# Embedded_II_MAIN_BOARD.net
KiCad netlist of a schematic drawn in EAGLE
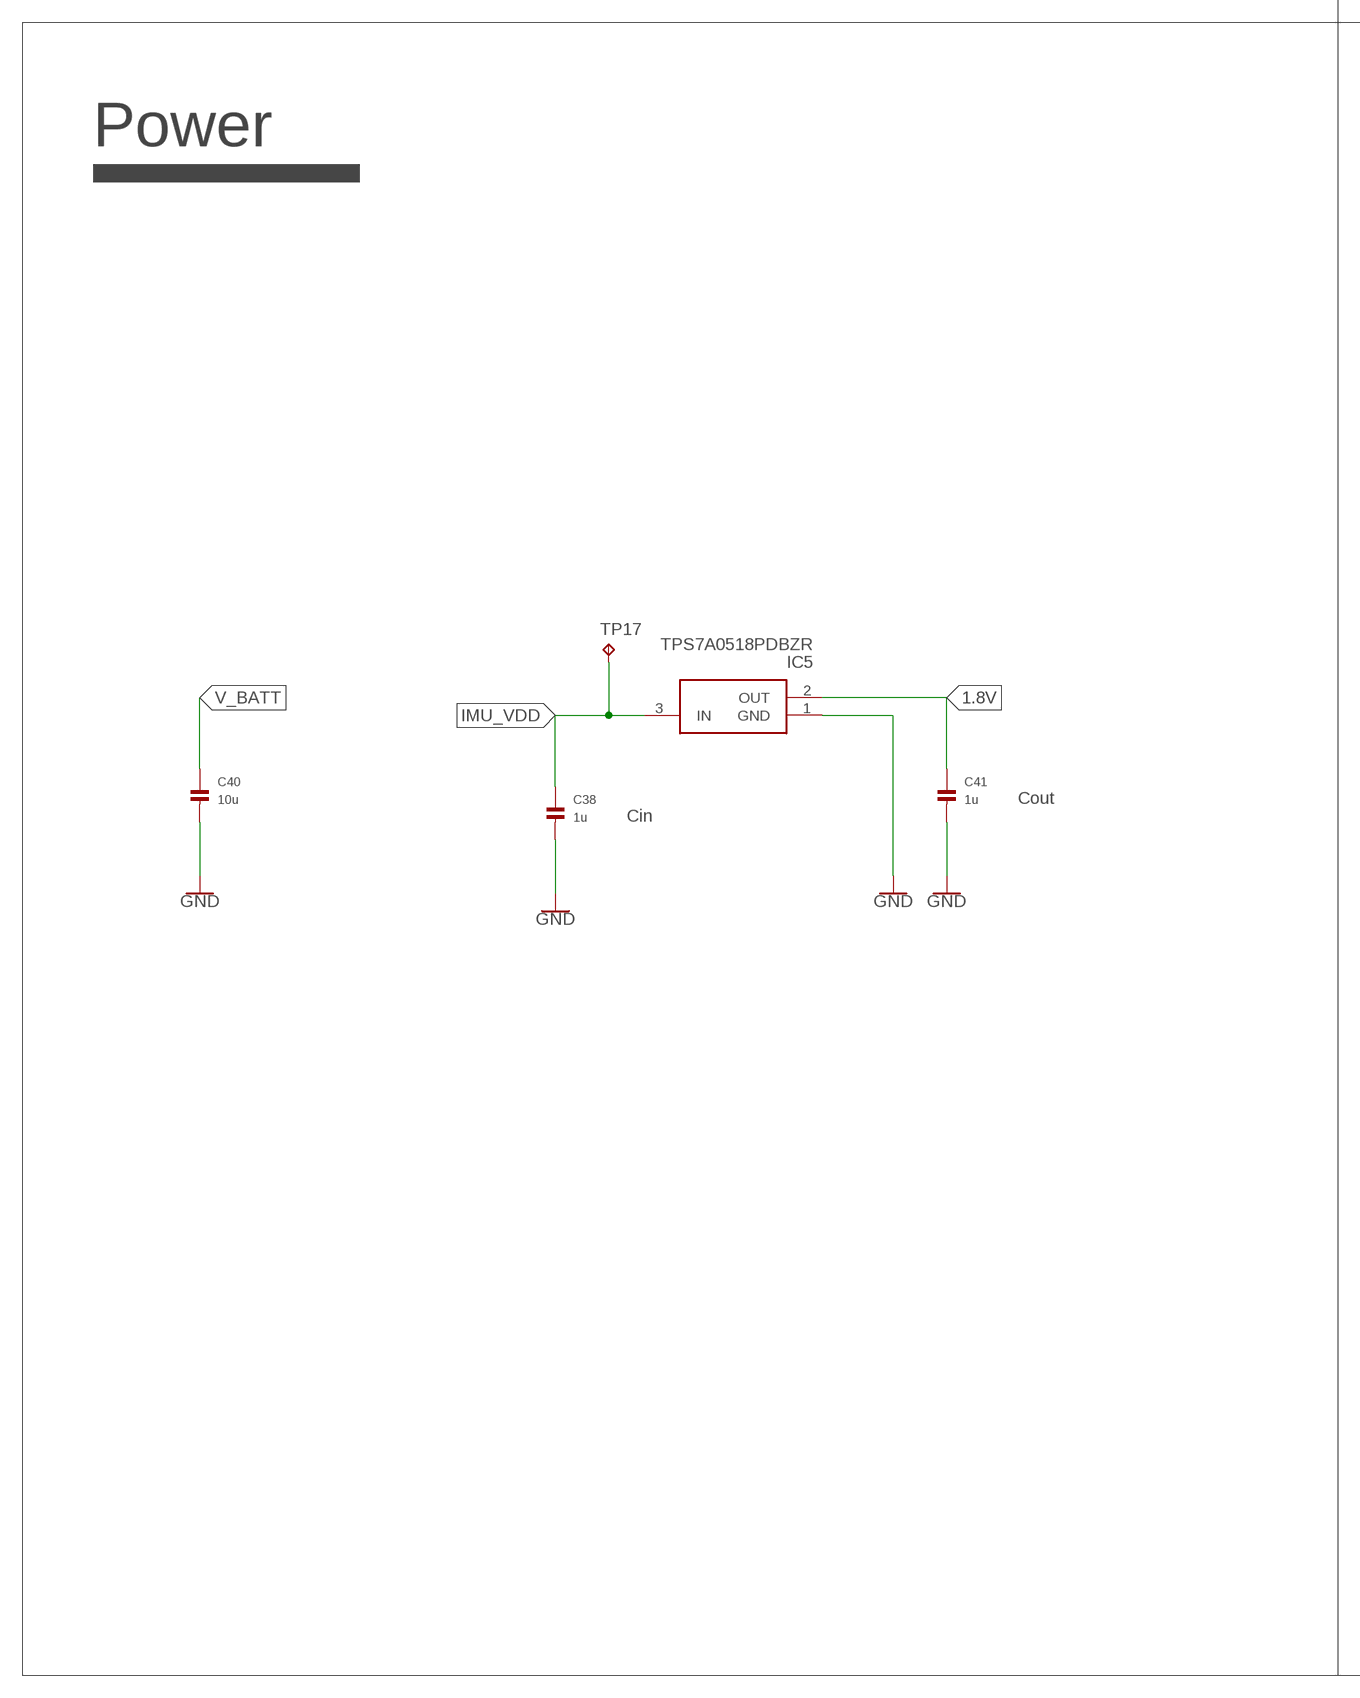
[diagram p0: schematic, sheet 1, part 1 of 2]
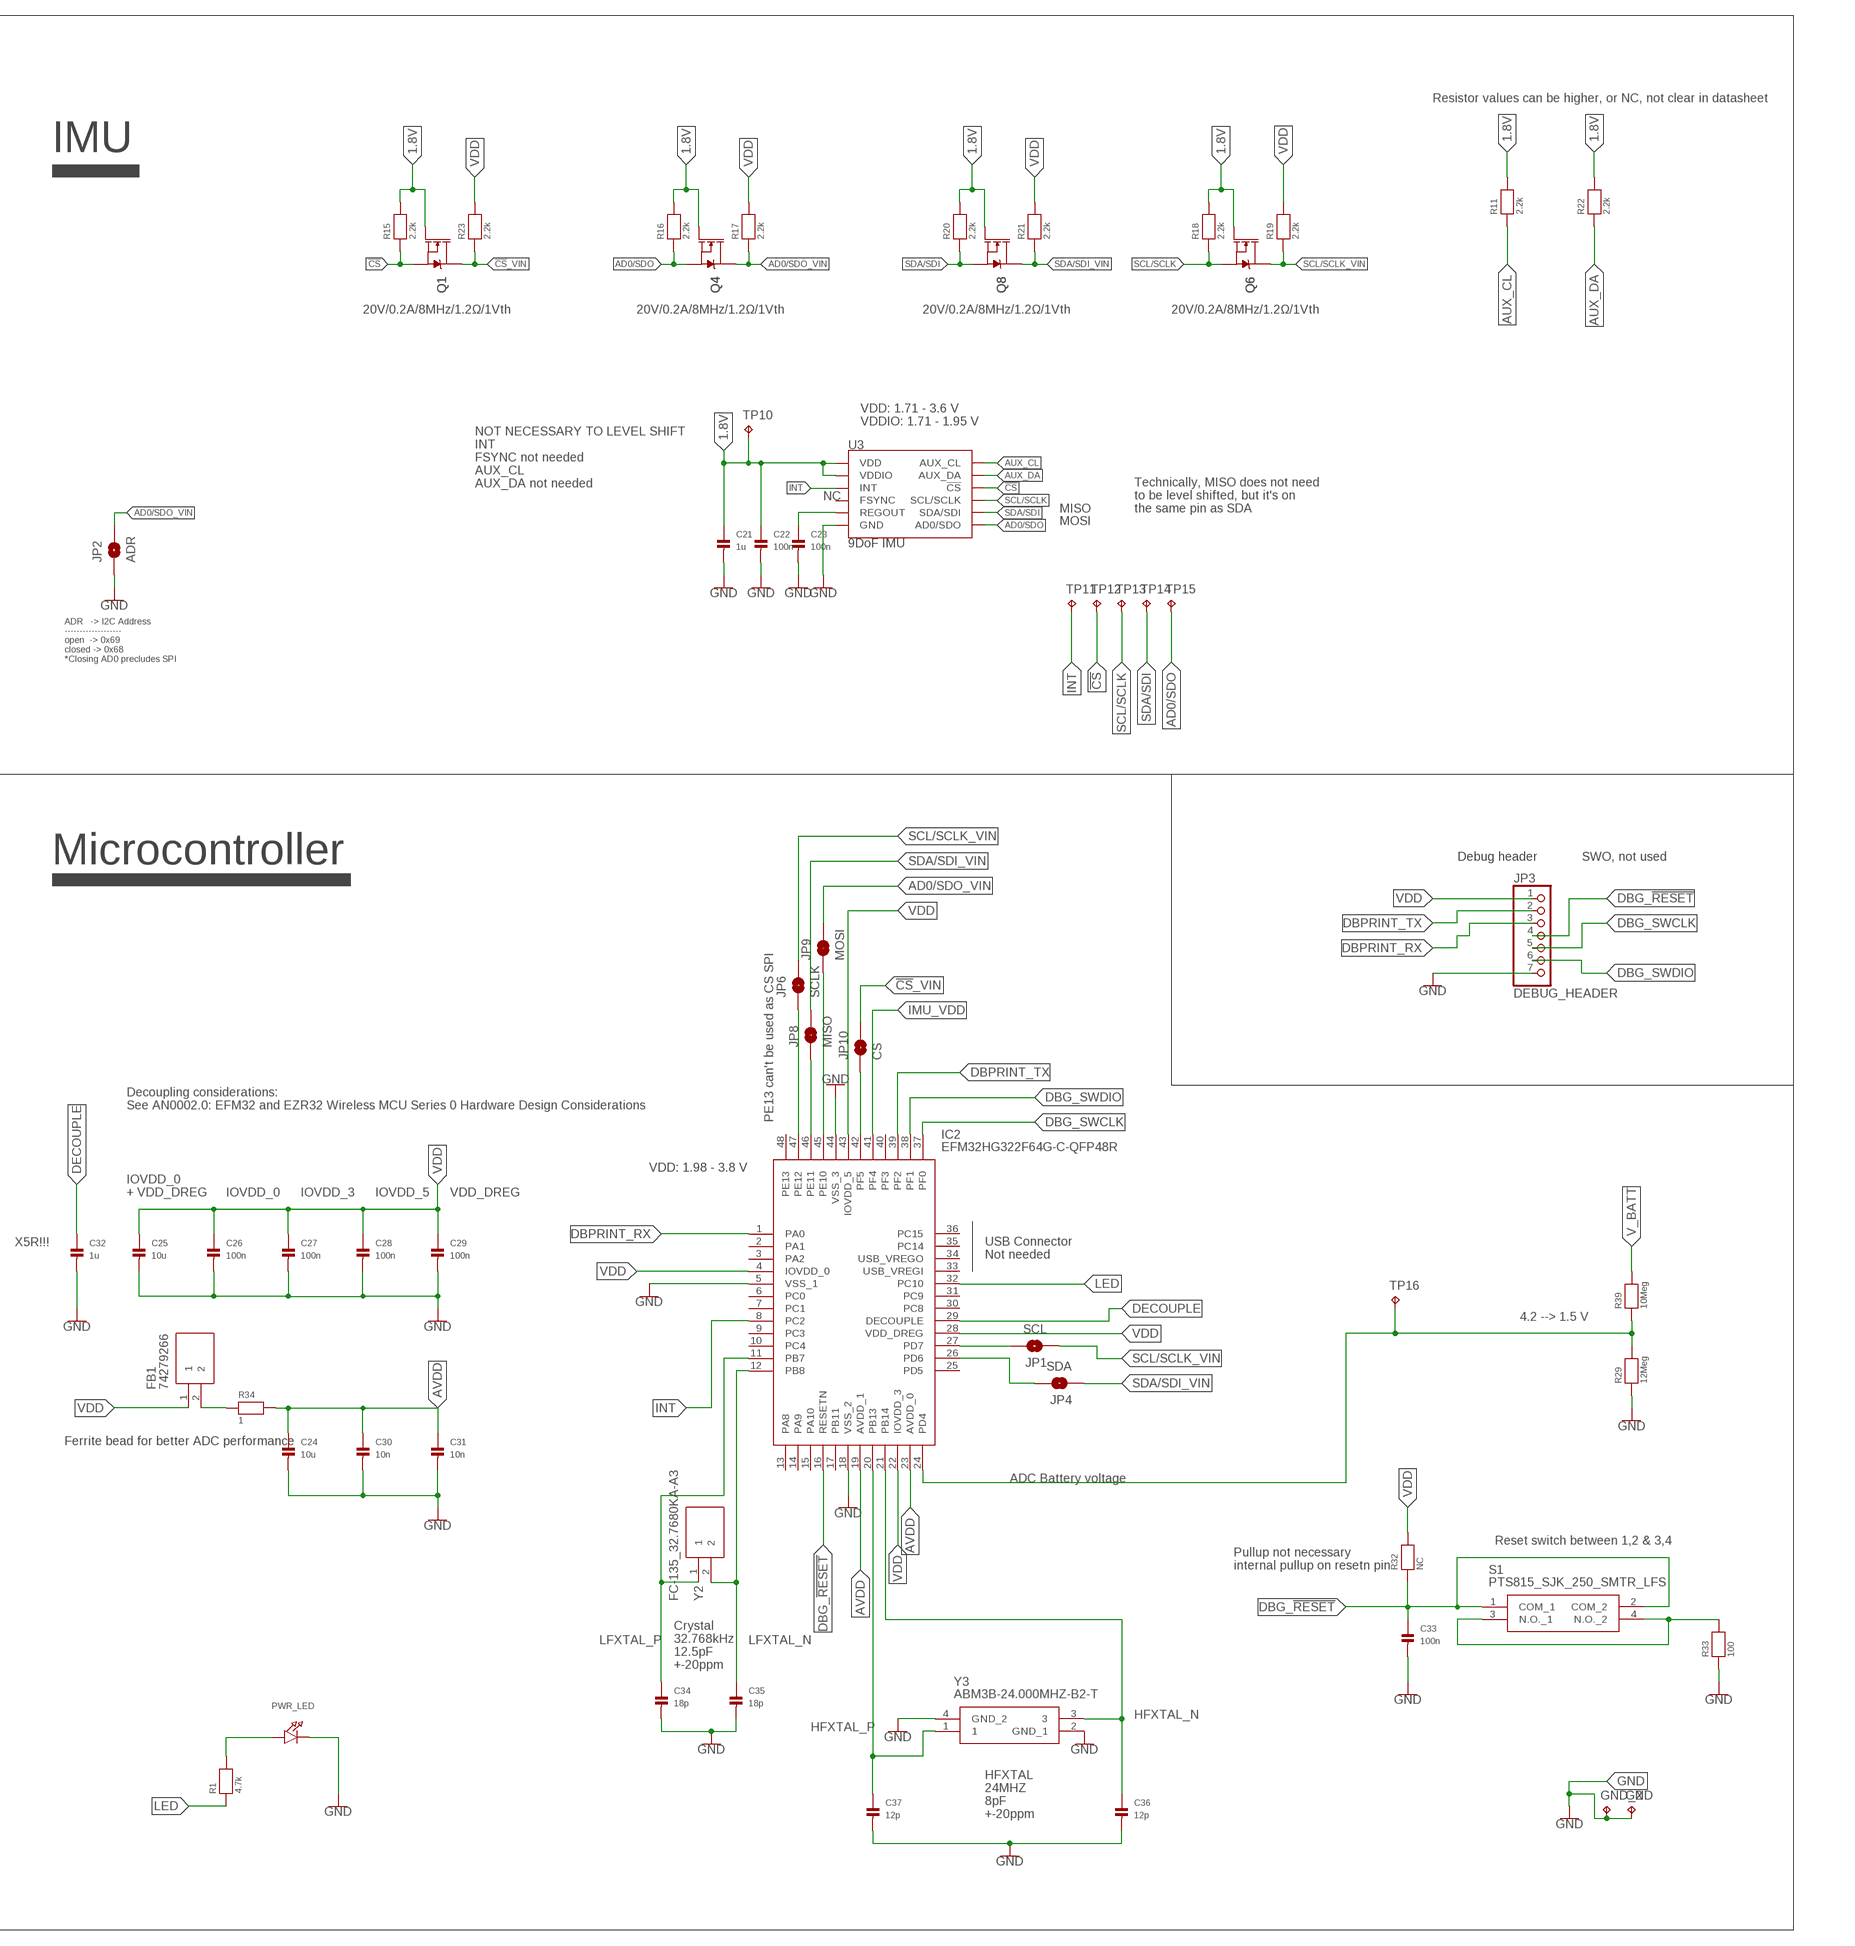
[diagram p1: schematic, sheet 1, part 2 of 2]

(export (version "E")
  (design (tool "Eeschema 10.0.6"))
  (components
    (comp (ref "C21")
      (value "1u")
      (footprint "eagle-import:0603")
      (libsource (lib "eagle-import") (part "CAP_CERAMIC0603"))
    )
    (comp (ref "C22")
      (value "100n")
      (footprint "eagle-import:0603")
      (libsource (lib "eagle-import") (part "CAP_CERAMIC0603"))
    )
    (comp (ref "C23")
      (value "100n")
      (footprint "eagle-import:0603")
      (libsource (lib "eagle-import") (part "CAP_CERAMIC0603"))
    )
    (comp (ref "C24")
      (value "10u")
      (footprint "eagle-import:0603")
      (libsource (lib "eagle-import") (part "CAP_CERAMIC0603"))
    )
    (comp (ref "C25")
      (value "10u")
      (footprint "eagle-import:0603")
      (libsource (lib "eagle-import") (part "CAP_CERAMIC0603"))
    )
    (comp (ref "C26")
      (value "100n")
      (footprint "eagle-import:0603")
      (libsource (lib "eagle-import") (part "CAP_CERAMIC0603"))
    )
    (comp (ref "C27")
      (value "100n")
      (footprint "eagle-import:0603")
      (libsource (lib "eagle-import") (part "CAP_CERAMIC0603"))
    )
    (comp (ref "C28")
      (value "100n")
      (footprint "eagle-import:0603")
      (libsource (lib "eagle-import") (part "CAP_CERAMIC0603"))
    )
    (comp (ref "C29")
      (value "100n")
      (footprint "eagle-import:0603")
      (libsource (lib "eagle-import") (part "CAP_CERAMIC0603"))
    )
    (comp (ref "C30")
      (value "10n")
      (footprint "eagle-import:0603")
      (libsource (lib "eagle-import") (part "CAP_CERAMIC0603"))
    )
    (comp (ref "C31")
      (value "10n")
      (footprint "eagle-import:0603")
      (libsource (lib "eagle-import") (part "CAP_CERAMIC0603"))
    )
    (comp (ref "C32")
      (value "1u")
      (footprint "eagle-import:0603")
      (libsource (lib "eagle-import") (part "CAP_CERAMIC0603"))
    )
    (comp (ref "C33")
      (value "100n")
      (footprint "eagle-import:0603")
      (libsource (lib "eagle-import") (part "CAP_CERAMIC0603"))
    )
    (comp (ref "C34")
      (value "18p")
      (footprint "eagle-import:0603")
      (libsource (lib "eagle-import") (part "CAP_CERAMIC0603"))
    )
    (comp (ref "C35")
      (value "18p")
      (footprint "eagle-import:0603")
      (libsource (lib "eagle-import") (part "CAP_CERAMIC0603"))
    )
    (comp (ref "C36")
      (value "12p")
      (footprint "eagle-import:0603")
      (libsource (lib "eagle-import") (part "CAP_CERAMIC0603"))
    )
    (comp (ref "C37")
      (value "12p")
      (footprint "eagle-import:0603")
      (libsource (lib "eagle-import") (part "CAP_CERAMIC0603"))
    )
    (comp (ref "C38")
      (value "1u")
      (footprint "eagle-import:0603")
      (libsource (lib "eagle-import") (part "CAP_CERAMIC0603"))
    )
    (comp (ref "C40")
      (value "10u")
      (footprint "eagle-import:0603")
      (libsource (lib "eagle-import") (part "CAP_CERAMIC0603"))
    )
    (comp (ref "C41")
      (value "1u")
      (footprint "eagle-import:0603")
      (libsource (lib "eagle-import") (part "CAP_CERAMIC0603"))
    )
    (comp (ref "FB1")
      (value "74279266")
      (footprint "eagle-import:BEADC1608X100N")
      (fields (field (name "MOUSER_PART_NUMBER") "710-74279266"))
      (libsource (lib "eagle-import") (part "74279266"))
    )
    (comp (ref "GND")
      (value "TPTP20SQ")
      (footprint "eagle-import:TP20SQ")
      (libsource (lib "eagle-import") (part "TPTP20SQ"))
    )
    (comp (ref "GND_2")
      (value "TPTP20SQ")
      (footprint "eagle-import:TP20SQ")
      (libsource (lib "eagle-import") (part "TPTP20SQ"))
    )
    (comp (ref "IC2")
      (value "EFM32HG322F64G-C-QFP48R")
      (footprint "eagle-import:QFP50P900X900X120-48N")
      (fields (field (name "MOUSER_PART_NUMBER") "634-HG322F64GCQFP48R"))
      (libsource (lib "eagle-import") (part "EFM32HG322F64G-C-QFP48R"))
    )
    (comp (ref "IC5")
      (value "TPS7A0518PDBZR")
      (footprint "eagle-import:SOT95P237X112-3N")
      (fields (field (name "MOUSER_PART_NUMBER") "595-TPS7A0518PDBZR"))
      (libsource (lib "eagle-import") (part "TPS7A0518PDBZR"))
    )
    (comp (ref "JP1")
      (value "SCL")
      (footprint "eagle-import:SMT-JUMPER_2_NO_SILK")
      (libsource (lib "eagle-import") (part "JUMPER-SMT_2_NO_SILK"))
    )
    (comp (ref "JP2")
      (value "ADR")
      (footprint "eagle-import:SMT-JUMPER_2_NO_SILK")
      (libsource (lib "eagle-import") (part "JUMPER-SMT_2_NO_SILK"))
    )
    (comp (ref "JP3")
      (value "DEBUG_HEADER")
      (footprint "eagle-import:1X07")
      (libsource (lib "eagle-import") (part "PINHD-1X7"))
    )
    (comp (ref "JP4")
      (value "SDA")
      (footprint "eagle-import:SMT-JUMPER_2_NO_SILK")
      (libsource (lib "eagle-import") (part "JUMPER-SMT_2_NO_SILK"))
    )
    (comp (ref "JP6")
      (value "SCLK")
      (footprint "eagle-import:SMT-JUMPER_2_NC_TRACE_SILK")
      (libsource (lib "eagle-import") (part "JUMPER-SMT_2_NC_TRACE_SILK"))
    )
    (comp (ref "JP8")
      (value "MISO")
      (footprint "eagle-import:SMT-JUMPER_2_NC_TRACE_SILK")
      (libsource (lib "eagle-import") (part "JUMPER-SMT_2_NC_TRACE_SILK"))
    )
    (comp (ref "JP9")
      (value "MOSI")
      (footprint "eagle-import:SMT-JUMPER_2_NC_TRACE_SILK")
      (libsource (lib "eagle-import") (part "JUMPER-SMT_2_NC_TRACE_SILK"))
    )
    (comp (ref "JP10")
      (value "CS")
      (footprint "eagle-import:SMT-JUMPER_2_NC_TRACE_SILK")
      (libsource (lib "eagle-import") (part "JUMPER-SMT_2_NC_TRACE_SILK"))
    )
    (comp (ref "PWR_LED")
      (value "LED0805")
      (footprint "eagle-import:CHIPLED_0805")
      (libsource (lib "eagle-import") (part "LED0805"))
    )
    (comp (ref "Q1")
      (value "20V/0.2A/8MHz/1.2Ω/1Vth")
      (footprint "eagle-import:SOT-416FL")
      (libsource (lib "eagle-import") (part "MOSFET-NCH-RE1C002UN"))
    )
    (comp (ref "Q4")
      (value "20V/0.2A/8MHz/1.2Ω/1Vth")
      (footprint "eagle-import:SOT-416FL")
      (libsource (lib "eagle-import") (part "MOSFET-NCH-RE1C002UN"))
    )
    (comp (ref "Q6")
      (value "20V/0.2A/8MHz/1.2Ω/1Vth")
      (footprint "eagle-import:SOT-416FL")
      (libsource (lib "eagle-import") (part "MOSFET-NCH-RE1C002UN"))
    )
    (comp (ref "Q8")
      (value "20V/0.2A/8MHz/1.2Ω/1Vth")
      (footprint "eagle-import:SOT-416FL")
      (libsource (lib "eagle-import") (part "MOSFET-NCH-RE1C002UN"))
    )
    (comp (ref "R1")
      (value "4.7k")
      (footprint "eagle-import:0603")
      (libsource (lib "eagle-import") (part "RESISTOR0603"))
    )
    (comp (ref "R11")
      (value "2.2k")
      (footprint "eagle-import:0603")
      (libsource (lib "eagle-import") (part "RESISTOR0603"))
    )
    (comp (ref "R15")
      (value "2.2k")
      (footprint "eagle-import:0603")
      (libsource (lib "eagle-import") (part "RESISTOR0603"))
    )
    (comp (ref "R16")
      (value "2.2k")
      (footprint "eagle-import:0603")
      (libsource (lib "eagle-import") (part "RESISTOR0603"))
    )
    (comp (ref "R17")
      (value "2.2k")
      (footprint "eagle-import:0603")
      (libsource (lib "eagle-import") (part "RESISTOR0603"))
    )
    (comp (ref "R18")
      (value "2.2k")
      (footprint "eagle-import:0603")
      (libsource (lib "eagle-import") (part "RESISTOR0603"))
    )
    (comp (ref "R19")
      (value "2.2k")
      (footprint "eagle-import:0603")
      (libsource (lib "eagle-import") (part "RESISTOR0603"))
    )
    (comp (ref "R20")
      (value "2.2k")
      (footprint "eagle-import:0603")
      (libsource (lib "eagle-import") (part "RESISTOR0603"))
    )
    (comp (ref "R21")
      (value "2.2k")
      (footprint "eagle-import:0603")
      (libsource (lib "eagle-import") (part "RESISTOR0603"))
    )
    (comp (ref "R22")
      (value "2.2k")
      (footprint "eagle-import:0603")
      (libsource (lib "eagle-import") (part "RESISTOR0603"))
    )
    (comp (ref "R23")
      (value "2.2k")
      (footprint "eagle-import:0603")
      (libsource (lib "eagle-import") (part "RESISTOR0603"))
    )
    (comp (ref "R29")
      (value "12Meg")
      (footprint "eagle-import:0603")
      (libsource (lib "eagle-import") (part "RESISTOR0603"))
    )
    (comp (ref "R32")
      (value "NC")
      (footprint "eagle-import:0603")
      (libsource (lib "eagle-import") (part "RESISTOR0603"))
    )
    (comp (ref "R33")
      (value "100")
      (footprint "eagle-import:0603")
      (libsource (lib "eagle-import") (part "RESISTOR0603"))
    )
    (comp (ref "R34")
      (value "1")
      (footprint "eagle-import:0603")
      (libsource (lib "eagle-import") (part "RESISTOR0603"))
    )
    (comp (ref "R39")
      (value "10Meg")
      (footprint "eagle-import:0603")
      (libsource (lib "eagle-import") (part "RESISTOR0603"))
    )
    (comp (ref "S1")
      (value "PTS815_SJK_250_SMTR_LFS")
      (footprint "eagle-import:PTS815SJK250SMTRLFS")
      (fields
        (field (name "MANUFACTURER_PART_NUMBER") "PTS815 SJK 250 SMTR LFS")
        (field (name "MOUSER_PART_NUMBER") "611-PTS815SJK250SMTR")
      )
      (libsource (lib "eagle-import") (part "PTS815_SJK_250_SMTR_LFS"))
    )
    (comp (ref "TP10")
      (value "TPTP10R")
      (footprint "eagle-import:TP10R")
      (libsource (lib "eagle-import") (part "TPTP10R"))
    )
    (comp (ref "TP11")
      (value "TPTP10R")
      (footprint "eagle-import:TP10R")
      (libsource (lib "eagle-import") (part "TPTP10R"))
    )
    (comp (ref "TP12")
      (value "TPTP10R")
      (footprint "eagle-import:TP10R")
      (libsource (lib "eagle-import") (part "TPTP10R"))
    )
    (comp (ref "TP13")
      (value "TPTP10R")
      (footprint "eagle-import:TP10R")
      (libsource (lib "eagle-import") (part "TPTP10R"))
    )
    (comp (ref "TP14")
      (value "TPTP10R")
      (footprint "eagle-import:TP10R")
      (libsource (lib "eagle-import") (part "TPTP10R"))
    )
    (comp (ref "TP15")
      (value "TPTP10R")
      (footprint "eagle-import:TP10R")
      (libsource (lib "eagle-import") (part "TPTP10R"))
    )
    (comp (ref "TP16")
      (value "TPTP10R")
      (footprint "eagle-import:TP10R")
      (libsource (lib "eagle-import") (part "TPTP10R"))
    )
    (comp (ref "TP17")
      (value "TPTP10R")
      (footprint "eagle-import:TP10R")
      (libsource (lib "eagle-import") (part "TPTP10R"))
    )
    (comp (ref "U3")
      (value "9DoF IMU")
      (footprint "eagle-import:SPARKFUN-SENSORS_QFN24-3X3")
      (libsource (lib "eagle-import") (part "SPARKFUN-SENSORS_ICM-20948"))
    )
    (comp (ref "Y2")
      (value "FC-135_32.7680KA-A3")
      (footprint "eagle-import:FC135327680KAAG0")
      (fields
        (field (name "MANUFACTURER_PART_NUMBER") "FC-135 32.7680KA-A3")
        (field (name "MOUSER_PART_NUMBER") "732-FC135-32.76KAA3")
      )
      (libsource (lib "eagle-import") (part "FC-135_32.7680KA-A3"))
    )
    (comp (ref "Y3")
      (value "ABM3B-24.000MHZ-B2-T")
      (footprint "eagle-import:ABM3B8000MHZ101UT")
      (fields (field (name "MOUSER_PART_NUMBER") "815-ABM3B-24-B2"))
      (libsource (lib "eagle-import") (part "ABM3B-24.000MHZ-B2-T"))
    )
  )
  (nets
    (net (code "1") (name "/DBG_~{RESET}") (class "Default")
      (node (ref "C33") (pin "1") (pinfunction "P$1_1") (pintype "passive"))
      (node (ref "IC2") (pin "16") (pinfunction "RESETN_16") (pintype "bidirectional"))
      (node (ref "JP3") (pin "4") (pinfunction "4_4") (pintype "passive"))
      (node (ref "R32") (pin "1") (pinfunction "1_1") (pintype "passive"))
      (node (ref "S1") (pin "1") (pinfunction "COM_1_1") (pintype "bidirectional"))
      (node (ref "S1") (pin "2") (pinfunction "COM_2_2") (pintype "bidirectional"))
    )
    (net (code "2") (name "/~{CS}") (class "Default")
      (node (ref "Q1") (pin "2") (pinfunction "S_2") (pintype "bidirectional"))
      (node (ref "R15") (pin "1") (pinfunction "1_1") (pintype "passive"))
      (node (ref "TP12") (pin "TP") (pinfunction "TP_TP") (pintype "input"))
      (node (ref "U3") (pin "22") (pinfunction "~{CS}_22") (pintype "bidirectional"))
    )
    (net (code "3") (name "/~{CS}_VIN") (class "Default")
      (node (ref "JP10") (pin "2") (pinfunction "2_2") (pintype "passive"))
      (node (ref "Q1") (pin "3") (pinfunction "D_3") (pintype "bidirectional"))
      (node (ref "R23") (pin "1") (pinfunction "1_1") (pintype "passive"))
    )
    (net (code "4") (name "1.8V") (class "Default")
      (node (ref "C21") (pin "1") (pinfunction "P$1_1") (pintype "passive"))
      (node (ref "C22") (pin "1") (pinfunction "P$1_1") (pintype "passive"))
      (node (ref "C41") (pin "1") (pinfunction "P$1_1") (pintype "passive"))
      (node (ref "IC5") (pin "2") (pinfunction "OUT_2") (pintype "bidirectional"))
      (node (ref "Q1") (pin "1") (pinfunction "G_1") (pintype "bidirectional"))
      (node (ref "Q4") (pin "1") (pinfunction "G_1") (pintype "bidirectional"))
      (node (ref "Q6") (pin "1") (pinfunction "G_1") (pintype "bidirectional"))
      (node (ref "Q8") (pin "1") (pinfunction "G_1") (pintype "bidirectional"))
      (node (ref "R11") (pin "2") (pinfunction "2_2") (pintype "passive"))
      (node (ref "R15") (pin "2") (pinfunction "2_2") (pintype "passive"))
      (node (ref "R16") (pin "2") (pinfunction "2_2") (pintype "passive"))
      (node (ref "R18") (pin "2") (pinfunction "2_2") (pintype "passive"))
      (node (ref "R20") (pin "2") (pinfunction "2_2") (pintype "passive"))
      (node (ref "R22") (pin "2") (pinfunction "2_2") (pintype "passive"))
      (node (ref "TP10") (pin "TP") (pinfunction "TP_TP") (pintype "input"))
      (node (ref "U3") (pin "13") (pinfunction "VDD_13") (pintype "bidirectional"))
      (node (ref "U3") (pin "8") (pinfunction "VDDIO_8") (pintype "bidirectional"))
    )
    (net (code "5") (name "AD0{slash}SDO") (class "Default")
      (node (ref "Q4") (pin "2") (pinfunction "S_2") (pintype "bidirectional"))
      (node (ref "R16") (pin "1") (pinfunction "1_1") (pintype "passive"))
      (node (ref "TP15") (pin "TP") (pinfunction "TP_TP") (pintype "input"))
      (node (ref "U3") (pin "9") (pinfunction "AD0/SDO_9") (pintype "bidirectional"))
    )
    (net (code "6") (name "AD0{slash}SDO_VIN") (class "Default")
      (node (ref "JP2") (pin "2") (pinfunction "2_2") (pintype "passive"))
      (node (ref "JP9") (pin "2") (pinfunction "2_2") (pintype "passive"))
      (node (ref "Q4") (pin "3") (pinfunction "D_3") (pintype "bidirectional"))
      (node (ref "R17") (pin "1") (pinfunction "1_1") (pintype "passive"))
    )
    (net (code "7") (name "AUX_CL") (class "Default")
      (node (ref "R11") (pin "1") (pinfunction "1_1") (pintype "passive"))
      (node (ref "U3") (pin "7") (pinfunction "AUX_CL_7") (pintype "bidirectional"))
    )
    (net (code "8") (name "AUX_DA") (class "Default")
      (node (ref "R22") (pin "1") (pinfunction "1_1") (pintype "passive"))
      (node (ref "U3") (pin "21") (pinfunction "AUX_DA_21") (pintype "bidirectional"))
    )
    (net (code "9") (name "AVDD") (class "Default")
      (node (ref "C24") (pin "1") (pinfunction "P$1_1") (pintype "passive"))
      (node (ref "C30") (pin "1") (pinfunction "P$1_1") (pintype "passive"))
      (node (ref "C31") (pin "1") (pinfunction "P$1_1") (pintype "passive"))
      (node (ref "IC2") (pin "19") (pinfunction "AVDD_1_19") (pintype "bidirectional"))
      (node (ref "IC2") (pin "23") (pinfunction "AVDD_0_23") (pintype "bidirectional"))
      (node (ref "R34") (pin "2") (pinfunction "2_2") (pintype "passive"))
    )
    (net (code "10") (name "DBG_SWCLK") (class "Default")
      (node (ref "IC2") (pin "37") (pinfunction "PF0_37") (pintype "bidirectional"))
      (node (ref "JP3") (pin "5") (pinfunction "5_5") (pintype "passive"))
    )
    (net (code "11") (name "DBG_SWDIO") (class "Default")
      (node (ref "IC2") (pin "38") (pinfunction "PF1_38") (pintype "bidirectional"))
      (node (ref "JP3") (pin "6") (pinfunction "6_6") (pintype "passive"))
    )
    (net (code "12") (name "DBPRINT_RX") (class "Default")
      (node (ref "IC2") (pin "1") (pinfunction "PA0_1") (pintype "bidirectional"))
      (node (ref "JP3") (pin "3") (pinfunction "3_3") (pintype "passive"))
    )
    (net (code "13") (name "DBPRINT_TX") (class "Default")
      (node (ref "IC2") (pin "39") (pinfunction "PF2_39") (pintype "bidirectional"))
      (node (ref "JP3") (pin "2") (pinfunction "2_2") (pintype "passive"))
    )
    (net (code "14") (name "DECOUPLE") (class "Default")
      (node (ref "C32") (pin "1") (pinfunction "P$1_1") (pintype "passive"))
      (node (ref "IC2") (pin "29") (pinfunction "DECOUPLE_29") (pintype "bidirectional"))
    )
    (net (code "15") (name "GND") (class "Default")
      (node (ref "C21") (pin "2") (pinfunction "P$2_2") (pintype "passive"))
      (node (ref "C22") (pin "2") (pinfunction "P$2_2") (pintype "passive"))
      (node (ref "C23") (pin "2") (pinfunction "P$2_2") (pintype "passive"))
      (node (ref "C24") (pin "2") (pinfunction "P$2_2") (pintype "passive"))
      (node (ref "C25") (pin "2") (pinfunction "P$2_2") (pintype "passive"))
      (node (ref "C26") (pin "2") (pinfunction "P$2_2") (pintype "passive"))
      (node (ref "C27") (pin "2") (pinfunction "P$2_2") (pintype "passive"))
      (node (ref "C28") (pin "2") (pinfunction "P$2_2") (pintype "passive"))
      (node (ref "C29") (pin "2") (pinfunction "P$2_2") (pintype "passive"))
      (node (ref "C30") (pin "2") (pinfunction "P$2_2") (pintype "passive"))
      (node (ref "C31") (pin "2") (pinfunction "P$2_2") (pintype "passive"))
      (node (ref "C32") (pin "2") (pinfunction "P$2_2") (pintype "passive"))
      (node (ref "C33") (pin "2") (pinfunction "P$2_2") (pintype "passive"))
      (node (ref "C34") (pin "2") (pinfunction "P$2_2") (pintype "passive"))
      (node (ref "C35") (pin "2") (pinfunction "P$2_2") (pintype "passive"))
      (node (ref "C36") (pin "2") (pinfunction "P$2_2") (pintype "passive"))
      (node (ref "C37") (pin "2") (pinfunction "P$2_2") (pintype "passive"))
      (node (ref "C38") (pin "2") (pinfunction "P$2_2") (pintype "passive"))
      (node (ref "C40") (pin "2") (pinfunction "P$2_2") (pintype "passive"))
      (node (ref "C41") (pin "2") (pinfunction "P$2_2") (pintype "passive"))
      (node (ref "GND") (pin "TP") (pinfunction "TP_TP") (pintype "input"))
      (node (ref "GND_2") (pin "TP") (pinfunction "TP_TP") (pintype "input"))
      (node (ref "IC2") (pin "18") (pinfunction "VSS_2_18") (pintype "bidirectional"))
      (node (ref "IC2") (pin "44") (pinfunction "VSS_3_44") (pintype "bidirectional"))
      (node (ref "IC2") (pin "5") (pinfunction "VSS_1_5") (pintype "bidirectional"))
      (node (ref "IC5") (pin "1") (pinfunction "GND_1") (pintype "bidirectional"))
      (node (ref "JP2") (pin "1") (pinfunction "1_1") (pintype "passive"))
      (node (ref "JP3") (pin "7") (pinfunction "7_7") (pintype "passive"))
      (node (ref "PWR_LED") (pin "C") (pinfunction "C_C") (pintype "passive"))
      (node (ref "R29") (pin "1") (pinfunction "1_1") (pintype "passive"))
      (node (ref "R33") (pin "1") (pinfunction "1_1") (pintype "passive"))
      (node (ref "U3") (pin "18") (pinfunction "GND_18") (pintype "bidirectional"))
      (node (ref "U3") (pin "20") (pinfunction "GND_20") (pintype "bidirectional"))
      (node (ref "Y3") (pin "2") (pinfunction "GND_1_2") (pintype "bidirectional"))
      (node (ref "Y3") (pin "4") (pinfunction "GND_2_4") (pintype "bidirectional"))
    )
    (net (code "16") (name "IMU_VDD") (class "Default")
      (node (ref "C38") (pin "1") (pinfunction "P$1_1") (pintype "passive"))
      (node (ref "IC2") (pin "41") (pinfunction "PF4_41") (pintype "bidirectional"))
      (node (ref "IC5") (pin "3") (pinfunction "IN_3") (pintype "bidirectional"))
      (node (ref "TP17") (pin "TP") (pinfunction "TP_TP") (pintype "input"))
    )
    (net (code "17") (name "INT") (class "Default")
      (node (ref "IC2") (pin "8") (pinfunction "PC2_8") (pintype "bidirectional"))
      (node (ref "TP11") (pin "TP") (pinfunction "TP_TP") (pintype "input"))
      (node (ref "U3") (pin "12") (pinfunction "INT_12") (pintype "bidirectional"))
    )
    (net (code "18") (name "LED") (class "Default")
      (node (ref "IC2") (pin "32") (pinfunction "PC10_32") (pintype "bidirectional"))
      (node (ref "R1") (pin "1") (pinfunction "1_1") (pintype "passive"))
    )
    (net (code "19") (name "Net-(C23-P$1)") (class "Default")
      (node (ref "C23") (pin "1") (pinfunction "P$1_1") (pintype "passive"))
      (node (ref "U3") (pin "10") (pinfunction "REGOUT_10") (pintype "bidirectional"))
    )
    (net (code "20") (name "Net-(C34-P$1)") (class "Default")
      (node (ref "C34") (pin "1") (pinfunction "P$1_1") (pintype "passive"))
      (node (ref "IC2") (pin "11") (pinfunction "PB7_11") (pintype "bidirectional"))
      (node (ref "Y2") (pin "1") (pinfunction "1_1") (pintype "bidirectional"))
    )
    (net (code "21") (name "Net-(C35-P$1)") (class "Default")
      (node (ref "C35") (pin "1") (pinfunction "P$1_1") (pintype "passive"))
      (node (ref "IC2") (pin "12") (pinfunction "PB8_12") (pintype "bidirectional"))
      (node (ref "Y2") (pin "2") (pinfunction "2_2") (pintype "bidirectional"))
    )
    (net (code "22") (name "Net-(C36-P$1)") (class "Default")
      (node (ref "C36") (pin "1") (pinfunction "P$1_1") (pintype "passive"))
      (node (ref "IC2") (pin "21") (pinfunction "PB14_21") (pintype "bidirectional"))
      (node (ref "Y3") (pin "3") (pinfunction "3_3") (pintype "bidirectional"))
    )
    (net (code "23") (name "Net-(C37-P$1)") (class "Default")
      (node (ref "C37") (pin "1") (pinfunction "P$1_1") (pintype "passive"))
      (node (ref "IC2") (pin "20") (pinfunction "PB13_20") (pintype "bidirectional"))
      (node (ref "Y3") (pin "1") (pinfunction "1_1") (pintype "bidirectional"))
    )
    (net (code "24") (name "Net-(FB1-Pad2)") (class "Default")
      (node (ref "FB1") (pin "2") (pinfunction "2_2") (pintype "bidirectional"))
      (node (ref "R34") (pin "1") (pinfunction "1_1") (pintype "passive"))
    )
    (net (code "25") (name "Net-(IC2-PD4)") (class "Default")
      (node (ref "IC2") (pin "24") (pinfunction "PD4_24") (pintype "bidirectional"))
      (node (ref "R29") (pin "2") (pinfunction "2_2") (pintype "passive"))
      (node (ref "R39") (pin "1") (pinfunction "1_1") (pintype "passive"))
      (node (ref "TP16") (pin "TP") (pinfunction "TP_TP") (pintype "input"))
    )
    (net (code "26") (name "Net-(IC2-PD6)") (class "Default")
      (node (ref "IC2") (pin "26") (pinfunction "PD6_26") (pintype "bidirectional"))
      (node (ref "JP4") (pin "2") (pinfunction "2_2") (pintype "passive"))
    )
    (net (code "27") (name "Net-(IC2-PD7)") (class "Default")
      (node (ref "IC2") (pin "27") (pinfunction "PD7_27") (pintype "bidirectional"))
      (node (ref "JP1") (pin "2") (pinfunction "2_2") (pintype "passive"))
    )
    (net (code "28") (name "Net-(IC2-PE10)") (class "Default")
      (node (ref "IC2") (pin "45") (pinfunction "PE10_45") (pintype "bidirectional"))
      (node (ref "JP9") (pin "1") (pinfunction "1_1") (pintype "passive"))
    )
    (net (code "29") (name "Net-(IC2-PE11)") (class "Default")
      (node (ref "IC2") (pin "46") (pinfunction "PE11_46") (pintype "bidirectional"))
      (node (ref "JP8") (pin "1") (pinfunction "1_1") (pintype "passive"))
    )
    (net (code "30") (name "Net-(IC2-PE12)") (class "Default")
      (node (ref "IC2") (pin "47") (pinfunction "PE12_47") (pintype "bidirectional"))
      (node (ref "JP6") (pin "1") (pinfunction "1_1") (pintype "passive"))
    )
    (net (code "31") (name "Net-(IC2-PF5)") (class "Default")
      (node (ref "IC2") (pin "42") (pinfunction "PF5_42") (pintype "bidirectional"))
      (node (ref "JP10") (pin "1") (pinfunction "1_1") (pintype "passive"))
    )
    (net (code "32") (name "Net-(PWR_LED-PadA)") (class "Default")
      (node (ref "PWR_LED") (pin "A") (pinfunction "A_A") (pintype "passive"))
      (node (ref "R1") (pin "2") (pinfunction "2_2") (pintype "passive"))
    )
    (net (code "33") (name "Net-(S1-N.O._1)") (class "Default")
      (node (ref "R33") (pin "2") (pinfunction "2_2") (pintype "passive"))
      (node (ref "S1") (pin "3") (pinfunction "N.O._1_3") (pintype "bidirectional"))
      (node (ref "S1") (pin "4") (pinfunction "N.O._2_4") (pintype "bidirectional"))
    )
    (net (code "34") (name "SCL{slash}SCLK") (class "Default")
      (node (ref "Q6") (pin "2") (pinfunction "S_2") (pintype "bidirectional"))
      (node (ref "R18") (pin "1") (pinfunction "1_1") (pintype "passive"))
      (node (ref "TP13") (pin "TP") (pinfunction "TP_TP") (pintype "input"))
      (node (ref "U3") (pin "23") (pinfunction "SCL/SCLK_23") (pintype "bidirectional"))
    )
    (net (code "35") (name "SCL{slash}SCLK_VIN") (class "Default")
      (node (ref "JP1") (pin "1") (pinfunction "1_1") (pintype "passive"))
      (node (ref "JP6") (pin "2") (pinfunction "2_2") (pintype "passive"))
      (node (ref "Q6") (pin "3") (pinfunction "D_3") (pintype "bidirectional"))
      (node (ref "R19") (pin "1") (pinfunction "1_1") (pintype "passive"))
    )
    (net (code "36") (name "SDA{slash}SDI") (class "Default")
      (node (ref "Q8") (pin "2") (pinfunction "S_2") (pintype "bidirectional"))
      (node (ref "R20") (pin "1") (pinfunction "1_1") (pintype "passive"))
      (node (ref "TP14") (pin "TP") (pinfunction "TP_TP") (pintype "input"))
      (node (ref "U3") (pin "24") (pinfunction "SDA/SDI_24") (pintype "bidirectional"))
    )
    (net (code "37") (name "SDA{slash}SDI_VIN") (class "Default")
      (node (ref "JP4") (pin "1") (pinfunction "1_1") (pintype "passive"))
      (node (ref "JP8") (pin "2") (pinfunction "2_2") (pintype "passive"))
      (node (ref "Q8") (pin "3") (pinfunction "D_3") (pintype "bidirectional"))
      (node (ref "R21") (pin "1") (pinfunction "1_1") (pintype "passive"))
    )
    (net (code "38") (name "VDD") (class "Default")
      (node (ref "C25") (pin "1") (pinfunction "P$1_1") (pintype "passive"))
      (node (ref "C26") (pin "1") (pinfunction "P$1_1") (pintype "passive"))
      (node (ref "C27") (pin "1") (pinfunction "P$1_1") (pintype "passive"))
      (node (ref "C28") (pin "1") (pinfunction "P$1_1") (pintype "passive"))
      (node (ref "C29") (pin "1") (pinfunction "P$1_1") (pintype "passive"))
      (node (ref "FB1") (pin "1") (pinfunction "1_1") (pintype "bidirectional"))
      (node (ref "IC2") (pin "22") (pinfunction "IOVDD_3_22") (pintype "bidirectional"))
      (node (ref "IC2") (pin "28") (pinfunction "VDD_DREG_28") (pintype "bidirectional"))
      (node (ref "IC2") (pin "4") (pinfunction "IOVDD_0_4") (pintype "bidirectional"))
      (node (ref "IC2") (pin "43") (pinfunction "IOVDD_5_43") (pintype "bidirectional"))
      (node (ref "JP3") (pin "1") (pinfunction "1_1") (pintype "passive"))
      (node (ref "R17") (pin "2") (pinfunction "2_2") (pintype "passive"))
      (node (ref "R19") (pin "2") (pinfunction "2_2") (pintype "passive"))
      (node (ref "R21") (pin "2") (pinfunction "2_2") (pintype "passive"))
      (node (ref "R23") (pin "2") (pinfunction "2_2") (pintype "passive"))
      (node (ref "R32") (pin "2") (pinfunction "2_2") (pintype "passive"))
    )
    (net (code "39") (name "V_BATT") (class "Default")
      (node (ref "C40") (pin "1") (pinfunction "P$1_1") (pintype "passive"))
      (node (ref "R39") (pin "2") (pinfunction "2_2") (pintype "passive"))
    )
    (net (code "40") (name "unconnected-(IC2-PA1-Pad2)") (class "Default")
      (node (ref "IC2") (pin "2") (pinfunction "PA1_2") (pintype "bidirectional"))
    )
    (net (code "41") (name "unconnected-(IC2-PA2-Pad3)") (class "Default")
      (node (ref "IC2") (pin "3") (pinfunction "PA2_3") (pintype "bidirectional"))
    )
    (net (code "42") (name "unconnected-(IC2-PA8-Pad13)") (class "Default")
      (node (ref "IC2") (pin "13") (pinfunction "PA8_13") (pintype "bidirectional"))
    )
    (net (code "43") (name "unconnected-(IC2-PA9-Pad14)") (class "Default")
      (node (ref "IC2") (pin "14") (pinfunction "PA9_14") (pintype "bidirectional"))
    )
    (net (code "44") (name "unconnected-(IC2-PA10-Pad15)") (class "Default")
      (node (ref "IC2") (pin "15") (pinfunction "PA10_15") (pintype "bidirectional"))
    )
    (net (code "45") (name "unconnected-(IC2-PB11-Pad17)") (class "Default")
      (node (ref "IC2") (pin "17") (pinfunction "PB11_17") (pintype "bidirectional"))
    )
    (net (code "46") (name "unconnected-(IC2-PC0-Pad6)") (class "Default")
      (node (ref "IC2") (pin "6") (pinfunction "PC0_6") (pintype "bidirectional"))
    )
    (net (code "47") (name "unconnected-(IC2-PC1-Pad7)") (class "Default")
      (node (ref "IC2") (pin "7") (pinfunction "PC1_7") (pintype "bidirectional"))
    )
    (net (code "48") (name "unconnected-(IC2-PC3-Pad9)") (class "Default")
      (node (ref "IC2") (pin "9") (pinfunction "PC3_9") (pintype "bidirectional"))
    )
    (net (code "49") (name "unconnected-(IC2-PC4-Pad10)") (class "Default")
      (node (ref "IC2") (pin "10") (pinfunction "PC4_10") (pintype "bidirectional"))
    )
    (net (code "50") (name "unconnected-(IC2-PC8-Pad30)") (class "Default")
      (node (ref "IC2") (pin "30") (pinfunction "PC8_30") (pintype "bidirectional"))
    )
    (net (code "51") (name "unconnected-(IC2-PC9-Pad31)") (class "Default")
      (node (ref "IC2") (pin "31") (pinfunction "PC9_31") (pintype "bidirectional"))
    )
    (net (code "52") (name "unconnected-(IC2-PC14-Pad35)") (class "Default")
      (node (ref "IC2") (pin "35") (pinfunction "PC14_35") (pintype "bidirectional"))
    )
    (net (code "53") (name "unconnected-(IC2-PC15-Pad36)") (class "Default")
      (node (ref "IC2") (pin "36") (pinfunction "PC15_36") (pintype "bidirectional"))
    )
    (net (code "54") (name "unconnected-(IC2-PD5-Pad25)") (class "Default")
      (node (ref "IC2") (pin "25") (pinfunction "PD5_25") (pintype "bidirectional"))
    )
    (net (code "55") (name "unconnected-(IC2-PE13-Pad48)") (class "Default")
      (node (ref "IC2") (pin "48") (pinfunction "PE13_48") (pintype "bidirectional"))
    )
    (net (code "56") (name "unconnected-(IC2-PF3-Pad40)") (class "Default")
      (node (ref "IC2") (pin "40") (pinfunction "PF3_40") (pintype "bidirectional"))
    )
    (net (code "57") (name "unconnected-(IC2-USB_VREGI-Pad33)") (class "Default")
      (node (ref "IC2") (pin "33") (pinfunction "USB_VREGI_33") (pintype "bidirectional"))
    )
    (net (code "58") (name "unconnected-(IC2-USB_VREGO-Pad34)") (class "Default")
      (node (ref "IC2") (pin "34") (pinfunction "USB_VREGO_34") (pintype "bidirectional"))
    )
    (net (code "59") (name "unconnected-(U3-FSYNC-Pad11)") (class "Default")
      (node (ref "U3") (pin "11") (pinfunction "FSYNC_11") (pintype "bidirectional"))
    )
  )
)
